# switch_v0_1.net
KiCad netlist of a schematic drawn in EAGLE
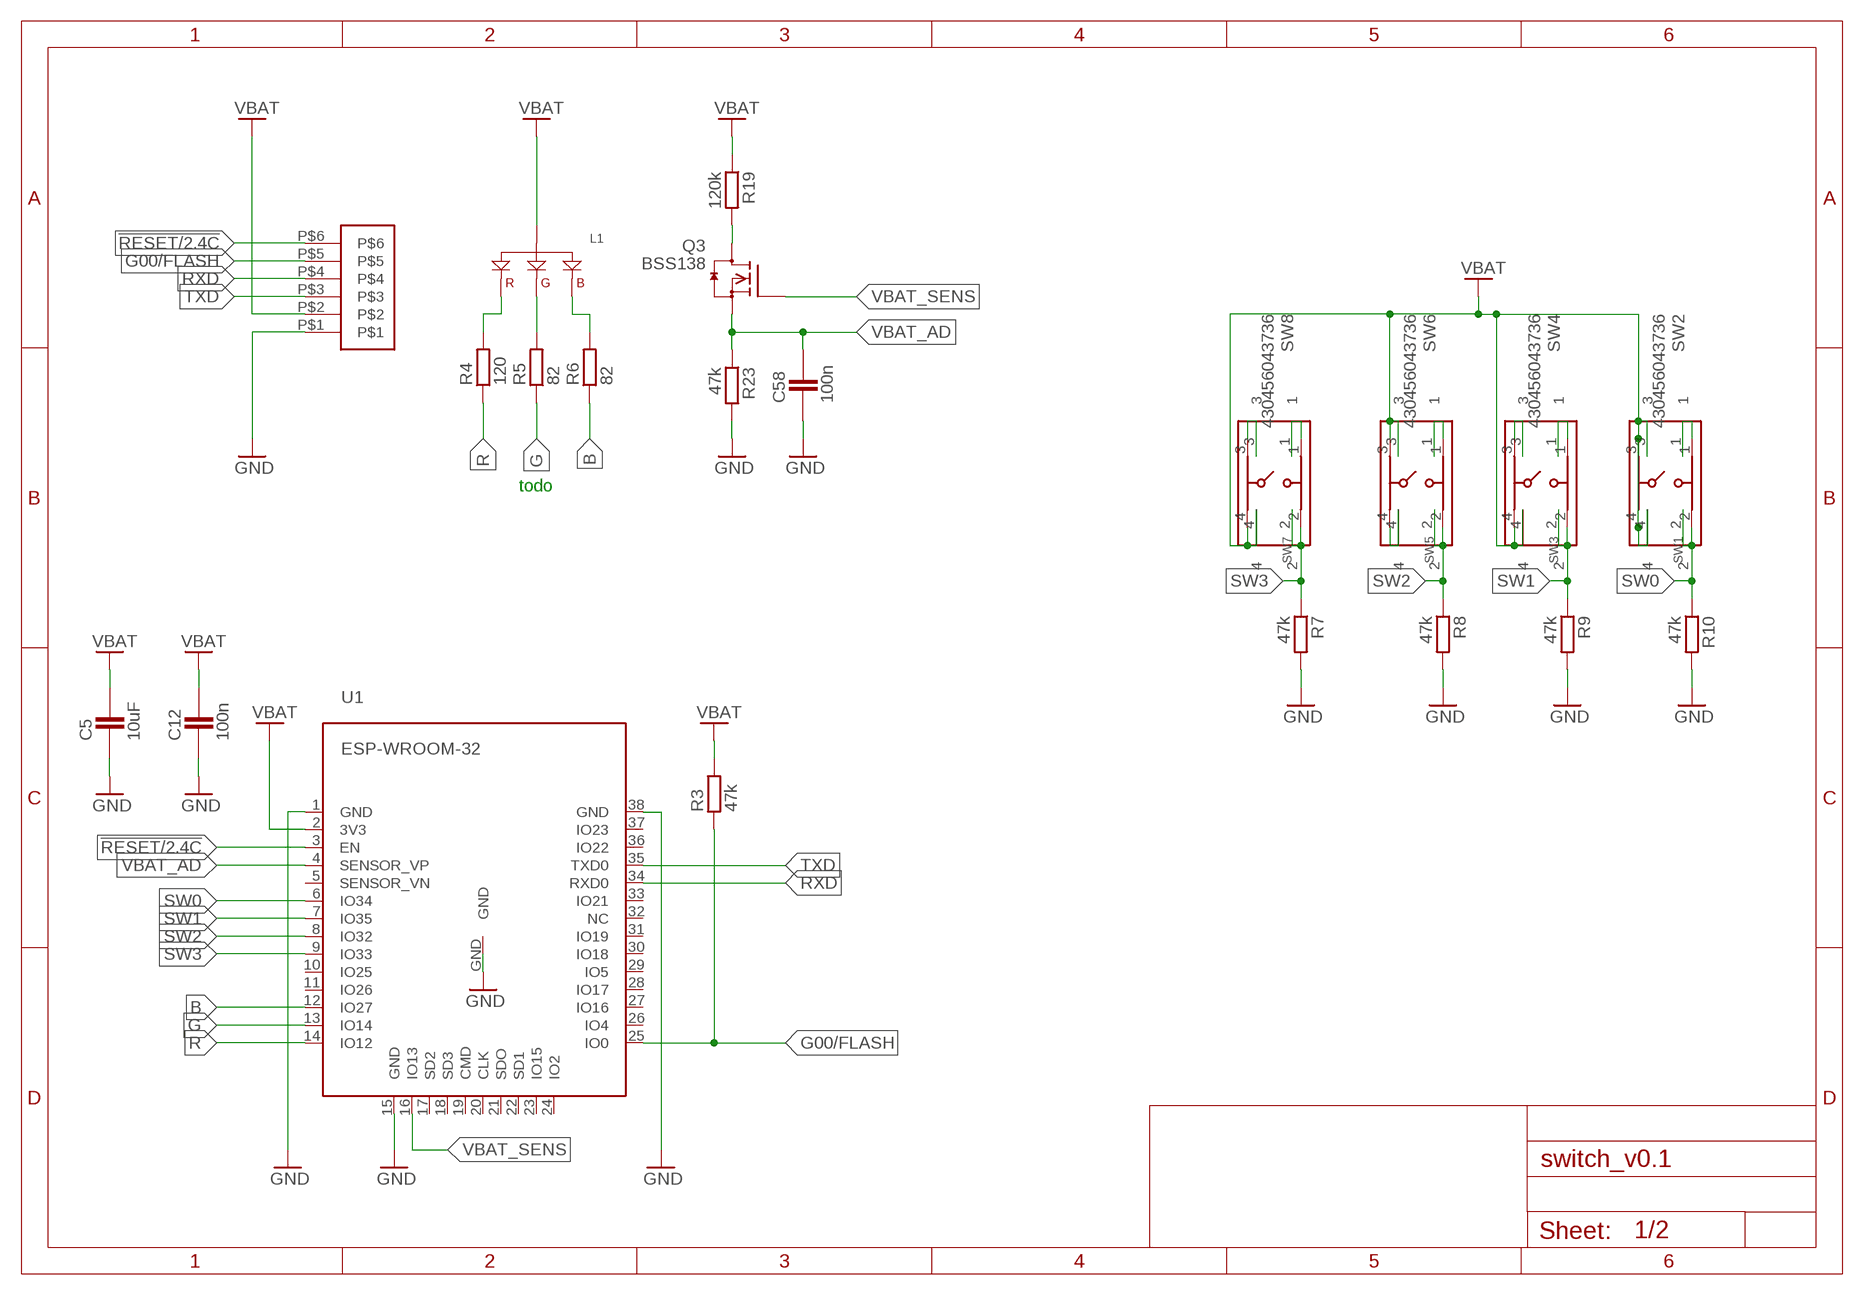
[diagram p0: schematic, sheet 1]
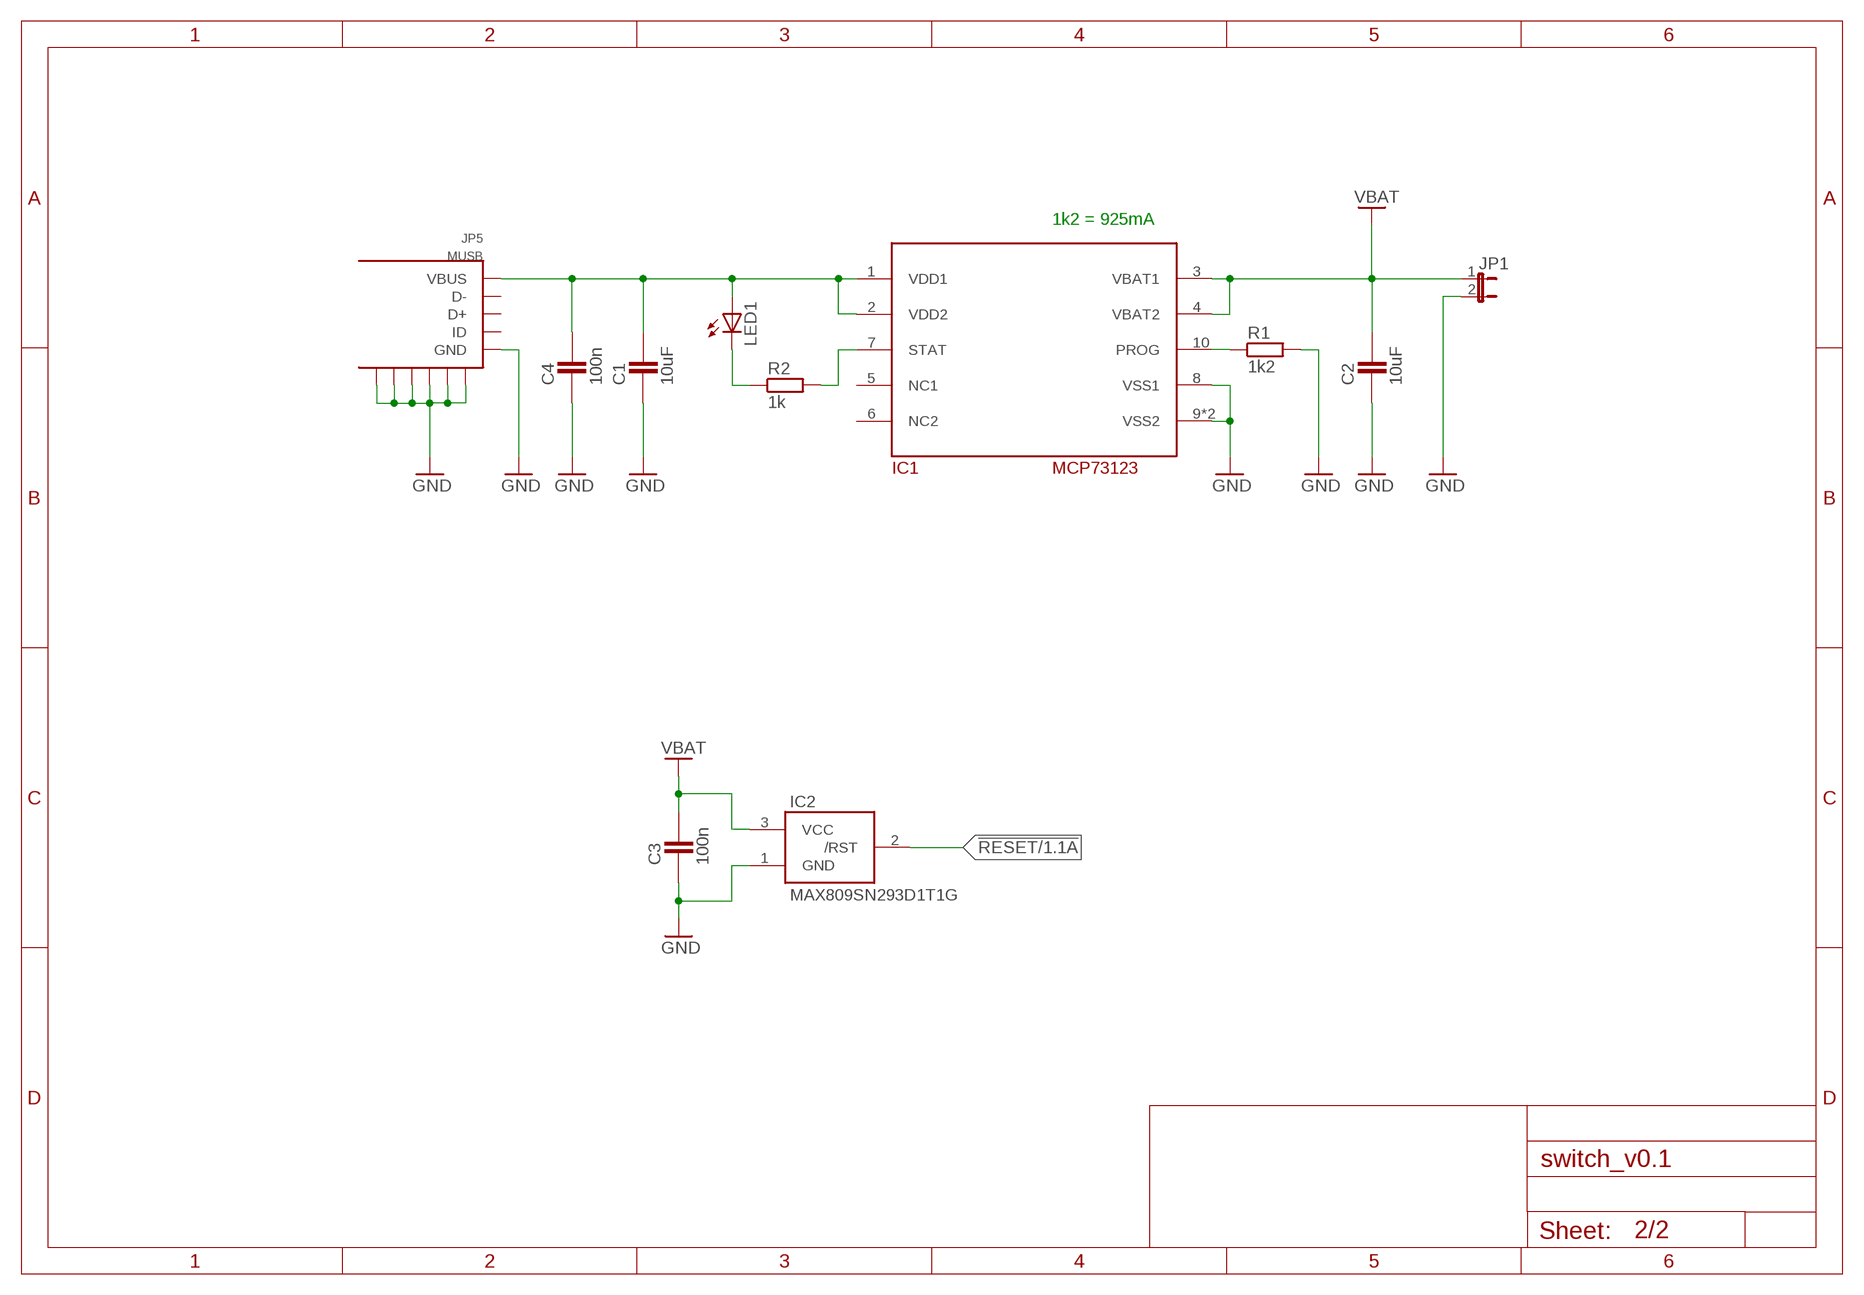
[diagram p1: schematic, sheet 2]

(export (version "E")
  (design (tool "Eeschema 10.0.6"))
  (components
    (comp (ref "C5")
      (value "10uF")
      (footprint "eagle-import:CAPC2012X145AN")
      (libsource (lib "eagle-import") (part "CAPACITOR_0805"))
    )
    (comp (ref "C12")
      (value "100n")
      (footprint "eagle-import:CAPC1005X60N")
      (libsource (lib "eagle-import") (part "CAPACITOR_0402"))
    )
    (comp (ref "C58")
      (value "100n")
      (footprint "eagle-import:CAPC1005X60N")
      (libsource (lib "eagle-import") (part "CAPACITOR_0402"))
    )
    (comp (ref "L1")
      (value "RGBLED_COMMONA")
      (footprint "eagle-import:LEDRGB")
      (libsource (lib "eagle-import") (part "RGBLED_COMMONA"))
    )
    (comp (ref "Q3")
      (value "BSS138")
      (footprint "eagle-import:SOT23")
      (libsource (lib "eagle-import") (part "BSS138"))
    )
    (comp (ref "R3")
      (value "47k")
      (footprint "eagle-import:RESC1005X40AN")
      (libsource (lib "eagle-import") (part "RESISTOR_0402"))
    )
    (comp (ref "R4")
      (value "120")
      (footprint "eagle-import:RESC2012X70N")
      (libsource (lib "eagle-import") (part "RESISTOR_0805"))
    )
    (comp (ref "R5")
      (value "82")
      (footprint "eagle-import:RESC2012X70N")
      (libsource (lib "eagle-import") (part "RESISTOR_0805"))
    )
    (comp (ref "R6")
      (value "82")
      (footprint "eagle-import:RESC2012X70N")
      (libsource (lib "eagle-import") (part "RESISTOR_0805"))
    )
    (comp (ref "R7")
      (value "47k")
      (footprint "eagle-import:RESC1005X40AN")
      (libsource (lib "eagle-import") (part "RESISTOR_0402"))
    )
    (comp (ref "R8")
      (value "47k")
      (footprint "eagle-import:RESC1005X40AN")
      (libsource (lib "eagle-import") (part "RESISTOR_0402"))
    )
    (comp (ref "R9")
      (value "47k")
      (footprint "eagle-import:RESC1005X40AN")
      (libsource (lib "eagle-import") (part "RESISTOR_0402"))
    )
    (comp (ref "R10")
      (value "47k")
      (footprint "eagle-import:RESC1005X40AN")
      (libsource (lib "eagle-import") (part "RESISTOR_0402"))
    )
    (comp (ref "R19")
      (value "120k")
      (footprint "eagle-import:RESC1005X40AN")
      (libsource (lib "eagle-import") (part "RESISTOR_0402"))
    )
    (comp (ref "R23")
      (value "47k")
      (footprint "eagle-import:RESC1005X40AN")
      (libsource (lib "eagle-import") (part "RESISTOR_0402"))
    )
    (comp (ref "SW1")
      (value "4301X20858X6")
      (footprint "eagle-import:4301X20858X6")
      (libsource (lib "eagle-import") (part "4301X20858X6"))
    )
    (comp (ref "SW2")
      (value "430456043736")
      (footprint "eagle-import:430456043736")
      (libsource (lib "eagle-import") (part "430456043736"))
    )
    (comp (ref "SW3")
      (value "4301X20858X6")
      (footprint "eagle-import:4301X20858X6")
      (libsource (lib "eagle-import") (part "4301X20858X6"))
    )
    (comp (ref "SW4")
      (value "430456043736")
      (footprint "eagle-import:430456043736")
      (libsource (lib "eagle-import") (part "430456043736"))
    )
    (comp (ref "SW5")
      (value "4301X20858X6")
      (footprint "eagle-import:4301X20858X6")
      (libsource (lib "eagle-import") (part "4301X20858X6"))
    )
    (comp (ref "SW6")
      (value "430456043736")
      (footprint "eagle-import:430456043736")
      (libsource (lib "eagle-import") (part "430456043736"))
    )
    (comp (ref "SW7")
      (value "4301X20858X6")
      (footprint "eagle-import:4301X20858X6")
      (libsource (lib "eagle-import") (part "4301X20858X6"))
    )
    (comp (ref "SW8")
      (value "430456043736")
      (footprint "eagle-import:430456043736")
      (libsource (lib "eagle-import") (part "430456043736"))
    )
    (comp (ref "U$3")
      (value "3X2-2.00RM")
      (footprint "eagle-import:3X2-2.00RM")
      (libsource (lib "eagle-import") (part "3X2-2.00RM"))
    )
    (comp (ref "U1")
      (value "ESP-WROOM-32")
      (footprint "eagle-import:ESP-WROOM-32")
      (libsource (lib "eagle-import") (part "ESP-WROOM-32"))
    )
    (comp (ref "C1")
      (value "10uF")
      (footprint "eagle-import:CAPC2012X145AN")
      (libsource (lib "eagle-import") (part "CAPACITOR_0805"))
    )
    (comp (ref "C2")
      (value "10uF")
      (footprint "eagle-import:CAPC2012X145AN")
      (libsource (lib "eagle-import") (part "CAPACITOR_0805"))
    )
    (comp (ref "C3")
      (value "100n")
      (footprint "eagle-import:CAPC1005X60N")
      (libsource (lib "eagle-import") (part "CAPACITOR_0402"))
    )
    (comp (ref "C4")
      (value "100n")
      (footprint "eagle-import:CAPC1005X60N")
      (libsource (lib "eagle-import") (part "CAPACITOR_0402"))
    )
    (comp (ref "IC1")
      (value "MCP73123")
      (footprint "eagle-import:DFN10-3X3")
      (libsource (lib "eagle-import") (part "MCP73123"))
    )
    (comp (ref "IC2")
      (value "MAX809SN293D1T1G")
      (footprint "eagle-import:SOT23")
      (libsource (lib "eagle-import") (part "MAX809EURJ"))
    )
    (comp (ref "JP1")
      (value "JP1E")
      (footprint "eagle-import:JP1")
      (libsource (lib "eagle-import") (part "JP1E"))
    )
    (comp (ref "JP5")
      (value "MUSB")
      (footprint "eagle-import:MICRO-USB")
      (libsource (lib "eagle-import") (part "MUSB"))
    )
    (comp (ref "LED1")
      (value "LEDCHIPLED_0805")
      (footprint "eagle-import:CHIPLED_0805")
      (libsource (lib "eagle-import") (part "LEDCHIPLED_0805"))
    )
    (comp (ref "R1")
      (value "1k2")
      (footprint "eagle-import:RESC1005X40AN")
      (libsource (lib "eagle-import") (part "RESISTOR_0402"))
    )
    (comp (ref "R2")
      (value "1k")
      (footprint "eagle-import:RESC1005X40AN")
      (libsource (lib "eagle-import") (part "RESISTOR_0402"))
    )
  )
  (nets
    (net (code "1") (name "B") (class "Default")
      (node (ref "R6") (pin "1") (pinfunction "1_1") (pintype "passive"))
      (node (ref "U1") (pin "12") (pinfunction "IO27_12") (pintype "bidirectional"))
    )
    (net (code "2") (name "G") (class "Default")
      (node (ref "R5") (pin "1") (pinfunction "1_1") (pintype "passive"))
      (node (ref "U1") (pin "13") (pinfunction "IO14_13") (pintype "bidirectional"))
    )
    (net (code "3") (name "G00{slash}FLASH") (class "Default")
      (node (ref "R3") (pin "1") (pinfunction "1_1") (pintype "passive"))
      (node (ref "U$3") (pin "P$5") (pinfunction "P$5_P$5") (pintype "bidirectional"))
      (node (ref "U1") (pin "25") (pinfunction "IO0_25") (pintype "bidirectional"))
    )
    (net (code "4") (name "GND") (class "Default")
      (node (ref "C1") (pin "1") (pinfunction "1_1") (pintype "passive"))
      (node (ref "C12") (pin "1") (pinfunction "1_1") (pintype "passive"))
      (node (ref "C2") (pin "1") (pinfunction "1_1") (pintype "passive"))
      (node (ref "C3") (pin "1") (pinfunction "1_1") (pintype "passive"))
      (node (ref "C4") (pin "1") (pinfunction "1_1") (pintype "passive"))
      (node (ref "C5") (pin "1") (pinfunction "1_1") (pintype "passive"))
      (node (ref "C58") (pin "1") (pinfunction "1_1") (pintype "passive"))
      (node (ref "IC1") (pin "8") (pinfunction "VSS1_8") (pintype "bidirectional"))
      (node (ref "IC1") (pin "9") (pinfunction "VSS2_9") (pintype "bidirectional"))
      (node (ref "IC1") (pin "EXP") (pinfunction "VSS2_EXP") (pintype "bidirectional"))
      (node (ref "IC2") (pin "1") (pinfunction "GND_1") (pintype "power_in"))
      (node (ref "JP1") (pin "2") (pinfunction "2_2") (pintype "passive"))
      (node (ref "JP5") (pin "G$1") (pinfunction "S1_G$1") (pintype "bidirectional"))
      (node (ref "JP5") (pin "G$2") (pinfunction "S2_G$2") (pintype "bidirectional"))
      (node (ref "JP5") (pin "G$3") (pinfunction "S3_G$3") (pintype "bidirectional"))
      (node (ref "JP5") (pin "G$4") (pinfunction "S4_G$4") (pintype "bidirectional"))
      (node (ref "JP5") (pin "P$5") (pinfunction "GND_P$5") (pintype "bidirectional"))
      (node (ref "JP5") (pin "S$1") (pinfunction "S5_S$1") (pintype "bidirectional"))
      (node (ref "JP5") (pin "S$2") (pinfunction "S6_S$2") (pintype "bidirectional"))
      (node (ref "R1") (pin "2") (pinfunction "2_2") (pintype "passive"))
      (node (ref "R10") (pin "2") (pinfunction "2_2") (pintype "passive"))
      (node (ref "R23") (pin "2") (pinfunction "2_2") (pintype "passive"))
      (node (ref "R7") (pin "2") (pinfunction "2_2") (pintype "passive"))
      (node (ref "R8") (pin "2") (pinfunction "2_2") (pintype "passive"))
      (node (ref "R9") (pin "2") (pinfunction "2_2") (pintype "passive"))
      (node (ref "U$3") (pin "P$1") (pinfunction "P$1_P$1") (pintype "bidirectional"))
      (node (ref "U1") (pin "1") (pinfunction "GND_1") (pintype "bidirectional"))
      (node (ref "U1") (pin "15") (pinfunction "GND_15") (pintype "bidirectional"))
      (node (ref "U1") (pin "38") (pinfunction "GND_38") (pintype "bidirectional"))
      (node (ref "U1") (pin "GND") (pinfunction "GND_GND") (pintype "bidirectional"))
    )
    (net (code "5") (name "Net-(IC1-PROG)") (class "Default")
      (node (ref "IC1") (pin "10") (pinfunction "PROG_10") (pintype "bidirectional"))
      (node (ref "R1") (pin "1") (pinfunction "1_1") (pintype "passive"))
    )
    (net (code "6") (name "Net-(IC1-STAT)") (class "Default")
      (node (ref "IC1") (pin "7") (pinfunction "STAT_7") (pintype "bidirectional"))
      (node (ref "R2") (pin "2") (pinfunction "2_2") (pintype "passive"))
    )
    (net (code "7") (name "Net-(IC1-VDD1)") (class "Default")
      (node (ref "C1") (pin "2") (pinfunction "2_2") (pintype "passive"))
      (node (ref "C4") (pin "2") (pinfunction "2_2") (pintype "passive"))
      (node (ref "IC1") (pin "1") (pinfunction "VDD1_1") (pintype "bidirectional"))
      (node (ref "IC1") (pin "2") (pinfunction "VDD2_2") (pintype "bidirectional"))
      (node (ref "JP5") (pin "P$1") (pinfunction "VBUS_P$1") (pintype "bidirectional"))
      (node (ref "LED1") (pin "A") (pinfunction "A_A") (pintype "passive"))
    )
    (net (code "8") (name "Net-(L1-B)") (class "Default")
      (node (ref "L1") (pin "4") (pinfunction "B_4") (pintype "bidirectional"))
      (node (ref "R6") (pin "2") (pinfunction "2_2") (pintype "passive"))
    )
    (net (code "9") (name "Net-(L1-G)") (class "Default")
      (node (ref "L1") (pin "3") (pinfunction "G_3") (pintype "bidirectional"))
      (node (ref "R5") (pin "2") (pinfunction "2_2") (pintype "passive"))
    )
    (net (code "10") (name "Net-(L1-R)") (class "Default")
      (node (ref "L1") (pin "1") (pinfunction "R_1") (pintype "bidirectional"))
      (node (ref "R4") (pin "2") (pinfunction "2_2") (pintype "passive"))
    )
    (net (code "11") (name "Net-(LED1-PadC)") (class "Default")
      (node (ref "LED1") (pin "C") (pinfunction "C_C") (pintype "passive"))
      (node (ref "R2") (pin "1") (pinfunction "1_1") (pintype "passive"))
    )
    (net (code "12") (name "Net-(Q3-D)") (class "Default")
      (node (ref "Q3") (pin "3") (pinfunction "D_3") (pintype "passive"))
      (node (ref "R19") (pin "2") (pinfunction "2_2") (pintype "passive"))
    )
    (net (code "13") (name "Net-(SW1-Pad1)") (class "Default")
      (node (ref "SW1") (pin "1") (pinfunction "1_1") (pintype "passive"))
      (node (ref "SW2") (pin "1") (pinfunction "1_1") (pintype "bidirectional"))
    )
    (net (code "14") (name "Net-(SW3-Pad1)") (class "Default")
      (node (ref "SW3") (pin "1") (pinfunction "1_1") (pintype "passive"))
      (node (ref "SW4") (pin "1") (pinfunction "1_1") (pintype "bidirectional"))
    )
    (net (code "15") (name "Net-(SW3-Pad3)") (class "Default")
      (node (ref "SW3") (pin "3") (pinfunction "3_3") (pintype "passive"))
      (node (ref "SW4") (pin "3") (pinfunction "3_3") (pintype "bidirectional"))
    )
    (net (code "16") (name "Net-(SW5-Pad1)") (class "Default")
      (node (ref "SW5") (pin "1") (pinfunction "1_1") (pintype "passive"))
      (node (ref "SW6") (pin "1") (pinfunction "1_1") (pintype "bidirectional"))
    )
    (net (code "17") (name "Net-(SW5-Pad4)") (class "Default")
      (node (ref "SW5") (pin "4") (pinfunction "4_4") (pintype "passive"))
      (node (ref "SW6") (pin "4") (pinfunction "4_4") (pintype "bidirectional"))
    )
    (net (code "18") (name "Net-(SW7-Pad1)") (class "Default")
      (node (ref "SW7") (pin "1") (pinfunction "1_1") (pintype "passive"))
      (node (ref "SW8") (pin "1") (pinfunction "1_1") (pintype "bidirectional"))
    )
    (net (code "19") (name "Net-(SW7-Pad3)") (class "Default")
      (node (ref "SW7") (pin "3") (pinfunction "3_3") (pintype "passive"))
      (node (ref "SW8") (pin "3") (pinfunction "3_3") (pintype "bidirectional"))
    )
    (net (code "20") (name "R") (class "Default")
      (node (ref "R4") (pin "1") (pinfunction "1_1") (pintype "passive"))
      (node (ref "U1") (pin "14") (pinfunction "IO12_14") (pintype "bidirectional"))
    )
    (net (code "21") (name "RXD") (class "Default")
      (node (ref "U$3") (pin "P$4") (pinfunction "P$4_P$4") (pintype "bidirectional"))
      (node (ref "U1") (pin "34") (pinfunction "RXD0_34") (pintype "bidirectional"))
    )
    (net (code "22") (name "SW0") (class "Default")
      (node (ref "R10") (pin "1") (pinfunction "1_1") (pintype "passive"))
      (node (ref "SW1") (pin "2") (pinfunction "2_2") (pintype "passive"))
      (node (ref "SW2") (pin "2") (pinfunction "2_2") (pintype "bidirectional"))
      (node (ref "U1") (pin "6") (pinfunction "IO34_6") (pintype "bidirectional"))
    )
    (net (code "23") (name "SW1") (class "Default")
      (node (ref "R9") (pin "1") (pinfunction "1_1") (pintype "passive"))
      (node (ref "SW3") (pin "2") (pinfunction "2_2") (pintype "passive"))
      (node (ref "SW4") (pin "2") (pinfunction "2_2") (pintype "bidirectional"))
      (node (ref "U1") (pin "7") (pinfunction "IO35_7") (pintype "bidirectional"))
    )
    (net (code "24") (name "SW2") (class "Default")
      (node (ref "R8") (pin "1") (pinfunction "1_1") (pintype "passive"))
      (node (ref "SW5") (pin "2") (pinfunction "2_2") (pintype "passive"))
      (node (ref "SW6") (pin "2") (pinfunction "2_2") (pintype "bidirectional"))
      (node (ref "U1") (pin "8") (pinfunction "IO32_8") (pintype "bidirectional"))
    )
    (net (code "25") (name "SW3") (class "Default")
      (node (ref "R7") (pin "1") (pinfunction "1_1") (pintype "passive"))
      (node (ref "SW7") (pin "2") (pinfunction "2_2") (pintype "passive"))
      (node (ref "SW8") (pin "2") (pinfunction "2_2") (pintype "bidirectional"))
      (node (ref "U1") (pin "9") (pinfunction "IO33_9") (pintype "bidirectional"))
    )
    (net (code "26") (name "TXD") (class "Default")
      (node (ref "U$3") (pin "P$3") (pinfunction "P$3_P$3") (pintype "bidirectional"))
      (node (ref "U1") (pin "35") (pinfunction "TXD0_35") (pintype "bidirectional"))
    )
    (net (code "27") (name "VBAT") (class "Default")
      (node (ref "C12") (pin "2") (pinfunction "2_2") (pintype "passive"))
      (node (ref "C2") (pin "2") (pinfunction "2_2") (pintype "passive"))
      (node (ref "C3") (pin "2") (pinfunction "2_2") (pintype "passive"))
      (node (ref "C5") (pin "2") (pinfunction "2_2") (pintype "passive"))
      (node (ref "IC1") (pin "3") (pinfunction "VBAT1_3") (pintype "bidirectional"))
      (node (ref "IC1") (pin "4") (pinfunction "VBAT2_4") (pintype "bidirectional"))
      (node (ref "IC2") (pin "3") (pinfunction "VCC_3") (pintype "input"))
      (node (ref "JP1") (pin "1") (pinfunction "1_1") (pintype "passive"))
      (node (ref "L1") (pin "2") (pinfunction "A_2") (pintype "bidirectional"))
      (node (ref "R19") (pin "1") (pinfunction "1_1") (pintype "passive"))
      (node (ref "R3") (pin "2") (pinfunction "2_2") (pintype "passive"))
      (node (ref "SW1") (pin "3") (pinfunction "3_3") (pintype "passive"))
      (node (ref "SW1") (pin "4") (pinfunction "4_4") (pintype "passive"))
      (node (ref "SW2") (pin "3") (pinfunction "3_3") (pintype "bidirectional"))
      (node (ref "SW2") (pin "4") (pinfunction "4_4") (pintype "bidirectional"))
      (node (ref "SW3") (pin "4") (pinfunction "4_4") (pintype "passive"))
      (node (ref "SW4") (pin "4") (pinfunction "4_4") (pintype "bidirectional"))
      (node (ref "SW5") (pin "3") (pinfunction "3_3") (pintype "passive"))
      (node (ref "SW6") (pin "3") (pinfunction "3_3") (pintype "bidirectional"))
      (node (ref "SW7") (pin "4") (pinfunction "4_4") (pintype "passive"))
      (node (ref "SW8") (pin "4") (pinfunction "4_4") (pintype "bidirectional"))
      (node (ref "U$3") (pin "P$2") (pinfunction "P$2_P$2") (pintype "bidirectional"))
      (node (ref "U1") (pin "2") (pinfunction "3V3_2") (pintype "bidirectional"))
    )
    (net (code "28") (name "VBAT_AD") (class "Default")
      (node (ref "C58") (pin "2") (pinfunction "2_2") (pintype "passive"))
      (node (ref "Q3") (pin "2") (pinfunction "S_2") (pintype "passive"))
      (node (ref "R23") (pin "1") (pinfunction "1_1") (pintype "passive"))
      (node (ref "U1") (pin "4") (pinfunction "SENSOR_VP_4") (pintype "bidirectional"))
    )
    (net (code "29") (name "VBAT_SENS") (class "Default")
      (node (ref "Q3") (pin "1") (pinfunction "G_1") (pintype "passive"))
      (node (ref "U1") (pin "16") (pinfunction "IO13_16") (pintype "bidirectional"))
    )
    (net (code "30") (name "unconnected-(IC1-NC1-Pad5)") (class "Default")
      (node (ref "IC1") (pin "5") (pinfunction "NC1_5") (pintype "bidirectional"))
    )
    (net (code "31") (name "unconnected-(IC1-NC2-Pad6)") (class "Default")
      (node (ref "IC1") (pin "6") (pinfunction "NC2_6") (pintype "bidirectional"))
    )
    (net (code "32") (name "unconnected-(JP5-D+-PadP$3)") (class "Default")
      (node (ref "JP5") (pin "P$3") (pinfunction "D+_P$3") (pintype "bidirectional"))
    )
    (net (code "33") (name "unconnected-(JP5-D--PadP$2)") (class "Default")
      (node (ref "JP5") (pin "P$2") (pinfunction "D-_P$2") (pintype "bidirectional"))
    )
    (net (code "34") (name "unconnected-(JP5-ID-PadP$4)") (class "Default")
      (node (ref "JP5") (pin "P$4") (pinfunction "ID_P$4") (pintype "bidirectional"))
    )
    (net (code "35") (name "unconnected-(U1-CLK-Pad20)") (class "Default")
      (node (ref "U1") (pin "20") (pinfunction "CLK_20") (pintype "bidirectional"))
    )
    (net (code "36") (name "unconnected-(U1-CMD-Pad19)") (class "Default")
      (node (ref "U1") (pin "19") (pinfunction "CMD_19") (pintype "bidirectional"))
    )
    (net (code "37") (name "unconnected-(U1-IO2-Pad24)") (class "Default")
      (node (ref "U1") (pin "24") (pinfunction "IO2_24") (pintype "bidirectional"))
    )
    (net (code "38") (name "unconnected-(U1-IO4-Pad26)") (class "Default")
      (node (ref "U1") (pin "26") (pinfunction "IO4_26") (pintype "bidirectional"))
    )
    (net (code "39") (name "unconnected-(U1-IO5-Pad29)") (class "Default")
      (node (ref "U1") (pin "29") (pinfunction "IO5_29") (pintype "bidirectional"))
    )
    (net (code "40") (name "unconnected-(U1-IO15-Pad23)") (class "Default")
      (node (ref "U1") (pin "23") (pinfunction "IO15_23") (pintype "bidirectional"))
    )
    (net (code "41") (name "unconnected-(U1-IO16-Pad27)") (class "Default")
      (node (ref "U1") (pin "27") (pinfunction "IO16_27") (pintype "bidirectional"))
    )
    (net (code "42") (name "unconnected-(U1-IO17-Pad28)") (class "Default")
      (node (ref "U1") (pin "28") (pinfunction "IO17_28") (pintype "bidirectional"))
    )
    (net (code "43") (name "unconnected-(U1-IO18-Pad30)") (class "Default")
      (node (ref "U1") (pin "30") (pinfunction "IO18_30") (pintype "bidirectional"))
    )
    (net (code "44") (name "unconnected-(U1-IO19-Pad31)") (class "Default")
      (node (ref "U1") (pin "31") (pinfunction "IO19_31") (pintype "bidirectional"))
    )
    (net (code "45") (name "unconnected-(U1-IO21-Pad33)") (class "Default")
      (node (ref "U1") (pin "33") (pinfunction "IO21_33") (pintype "bidirectional"))
    )
    (net (code "46") (name "unconnected-(U1-IO22-Pad36)") (class "Default")
      (node (ref "U1") (pin "36") (pinfunction "IO22_36") (pintype "bidirectional"))
    )
    (net (code "47") (name "unconnected-(U1-IO23-Pad37)") (class "Default")
      (node (ref "U1") (pin "37") (pinfunction "IO23_37") (pintype "bidirectional"))
    )
    (net (code "48") (name "unconnected-(U1-IO25-Pad10)") (class "Default")
      (node (ref "U1") (pin "10") (pinfunction "IO25_10") (pintype "bidirectional"))
    )
    (net (code "49") (name "unconnected-(U1-IO26-Pad11)") (class "Default")
      (node (ref "U1") (pin "11") (pinfunction "IO26_11") (pintype "bidirectional"))
    )
    (net (code "50") (name "unconnected-(U1-NC-Pad32)") (class "Default")
      (node (ref "U1") (pin "32") (pinfunction "NC_32") (pintype "bidirectional"))
    )
    (net (code "51") (name "unconnected-(U1-SD1-Pad22)") (class "Default")
      (node (ref "U1") (pin "22") (pinfunction "SD1_22") (pintype "bidirectional"))
    )
    (net (code "52") (name "unconnected-(U1-SD2-Pad17)") (class "Default")
      (node (ref "U1") (pin "17") (pinfunction "SD2_17") (pintype "bidirectional"))
    )
    (net (code "53") (name "unconnected-(U1-SD3-Pad18)") (class "Default")
      (node (ref "U1") (pin "18") (pinfunction "SD3_18") (pintype "bidirectional"))
    )
    (net (code "54") (name "unconnected-(U1-SDO-Pad21)") (class "Default")
      (node (ref "U1") (pin "21") (pinfunction "SDO_21") (pintype "bidirectional"))
    )
    (net (code "55") (name "unconnected-(U1-SENSOR_VN-Pad5)") (class "Default")
      (node (ref "U1") (pin "5") (pinfunction "SENSOR_VN_5") (pintype "bidirectional"))
    )
    (net (code "56") (name "~{RESET}") (class "Default")
      (node (ref "IC2") (pin "2") (pinfunction "/RST_2") (pintype "output"))
      (node (ref "U$3") (pin "P$6") (pinfunction "P$6_P$6") (pintype "bidirectional"))
      (node (ref "U1") (pin "3") (pinfunction "EN_3") (pintype "bidirectional"))
    )
  )
)
